# POWER.net
KiCad netlist of a schematic drawn in Altium Designer
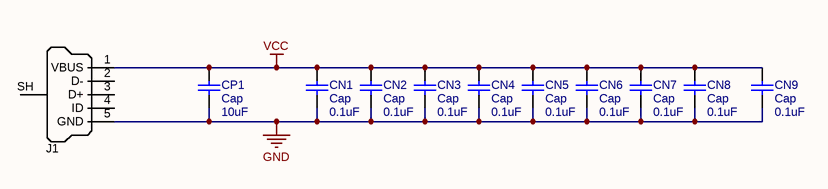
[diagram p0: POWER.SchDoc]

(export (version "E")
  (design (tool "Eeschema 10.0.6"))
  (components
    (comp (ref "CN1")
      (value "Cap")
      (footprint "CAPR10.16-11.5x3.6")
      (description "Capacitor")
      (fields (field (name "ALTIUM_VALUE") "0.1uF") (field (name "PUBLISHER") "Altium Limited"))
      (libsource (lib "Miscellaneous Devices") (part "Cap"))
    )
    (comp (ref "CN2")
      (value "Cap")
      (footprint "CAPR10.16-11.5x3.6")
      (description "Capacitor")
      (fields (field (name "ALTIUM_VALUE") "0.1uF") (field (name "PUBLISHER") "Altium Limited"))
      (libsource (lib "Miscellaneous Devices") (part "Cap"))
    )
    (comp (ref "CN3")
      (value "Cap")
      (footprint "CAPR10.16-11.5x3.6")
      (description "Capacitor")
      (fields (field (name "ALTIUM_VALUE") "0.1uF") (field (name "PUBLISHER") "Altium Limited"))
      (libsource (lib "Miscellaneous Devices") (part "Cap"))
    )
    (comp (ref "CN4")
      (value "Cap")
      (footprint "CAPR10.16-11.5x3.6")
      (description "Capacitor")
      (fields (field (name "ALTIUM_VALUE") "0.1uF") (field (name "PUBLISHER") "Altium Limited"))
      (libsource (lib "Miscellaneous Devices") (part "Cap"))
    )
    (comp (ref "CN5")
      (value "Cap")
      (footprint "CAPR10.16-11.5x3.6")
      (description "Capacitor")
      (fields (field (name "ALTIUM_VALUE") "0.1uF") (field (name "PUBLISHER") "Altium Limited"))
      (libsource (lib "Miscellaneous Devices") (part "Cap"))
    )
    (comp (ref "CN6")
      (value "Cap")
      (footprint "CAPR10.16-11.5x3.6")
      (description "Capacitor")
      (fields (field (name "ALTIUM_VALUE") "0.1uF") (field (name "PUBLISHER") "Altium Limited"))
      (libsource (lib "Miscellaneous Devices") (part "Cap"))
    )
    (comp (ref "CN7")
      (value "Cap")
      (footprint "CAPR10.16-11.5x3.6")
      (description "Capacitor")
      (fields (field (name "ALTIUM_VALUE") "0.1uF") (field (name "PUBLISHER") "Altium Limited"))
      (libsource (lib "Miscellaneous Devices") (part "Cap"))
    )
    (comp (ref "CN8")
      (value "Cap")
      (footprint "CAPR10.16-11.5x3.6")
      (description "Capacitor")
      (fields (field (name "ALTIUM_VALUE") "0.1uF") (field (name "PUBLISHER") "Altium Limited"))
      (libsource (lib "Miscellaneous Devices") (part "Cap"))
    )
    (comp (ref "CN9")
      (value "Cap")
      (footprint "CAPR10.16-11.5x3.6")
      (description "Capacitor")
      (fields (field (name "ALTIUM_VALUE") "0.1uF") (field (name "PUBLISHER") "Altium Limited"))
      (libsource (lib "Miscellaneous Devices") (part "Cap"))
    )
    (comp (ref "CP1")
      (value "Cap")
      (footprint "CAPE3.5mm")
      (description "Capacitor")
      (fields (field (name "ALTIUM_VALUE") "10uF") (field (name "PUBLISHER") "Altium Limited"))
      (libsource (lib "Miscellaneous Devices") (part "Cap"))
    )
    (comp (ref "J1")
      (value "USB Micro Type B (recommended if hand soldering)")
      (footprint "USB Micro B SMD")
      (description "Connector SMD-THD USB Micro Type B middle mount")
      (libsource (lib "PBL - Connectors") (part "USB_Micro_TypeB_FCI"))
    )
  )
  (nets
    (net (code "1") (name "GND") (class "Default")
      (node (ref "CN1") (pin "1") (pinfunction "1_1") (pintype "passive"))
      (node (ref "CN2") (pin "1") (pinfunction "1_1") (pintype "passive"))
      (node (ref "CN3") (pin "1") (pinfunction "1_1") (pintype "passive"))
      (node (ref "CN4") (pin "1") (pinfunction "1_1") (pintype "passive"))
      (node (ref "CN5") (pin "1") (pinfunction "1_1") (pintype "passive"))
      (node (ref "CN6") (pin "1") (pinfunction "1_1") (pintype "passive"))
      (node (ref "CN7") (pin "1") (pinfunction "1_1") (pintype "passive"))
      (node (ref "CN8") (pin "1") (pinfunction "1_1") (pintype "passive"))
      (node (ref "CN9") (pin "1") (pinfunction "1_1") (pintype "passive"))
      (node (ref "CP1") (pin "2") (pinfunction "2_2") (pintype "passive"))
      (node (ref "J1") (pin "5") (pinfunction "GND_5") (pintype "passive"))
    )
    (net (code "2") (name "VCC") (class "Default")
      (node (ref "CN1") (pin "2") (pinfunction "2_2") (pintype "passive"))
      (node (ref "CN2") (pin "2") (pinfunction "2_2") (pintype "passive"))
      (node (ref "CN3") (pin "2") (pinfunction "2_2") (pintype "passive"))
      (node (ref "CN4") (pin "2") (pinfunction "2_2") (pintype "passive"))
      (node (ref "CN5") (pin "2") (pinfunction "2_2") (pintype "passive"))
      (node (ref "CN6") (pin "2") (pinfunction "2_2") (pintype "passive"))
      (node (ref "CN7") (pin "2") (pinfunction "2_2") (pintype "passive"))
      (node (ref "CN8") (pin "2") (pinfunction "2_2") (pintype "passive"))
      (node (ref "CN9") (pin "2") (pinfunction "2_2") (pintype "passive"))
      (node (ref "CP1") (pin "1") (pinfunction "1_1") (pintype "passive"))
      (node (ref "J1") (pin "1") (pinfunction "VBUS_1") (pintype "passive"))
    )
    (net (code "3") (name "unconnected-(J1-D+-Pad3)") (class "Default")
      (node (ref "J1") (pin "3") (pinfunction "D+_3") (pintype "passive"))
    )
    (net (code "4") (name "unconnected-(J1-D--Pad2)") (class "Default")
      (node (ref "J1") (pin "2") (pinfunction "D-_2") (pintype "passive"))
    )
    (net (code "5") (name "unconnected-(J1-ID-Pad4)") (class "Default")
      (node (ref "J1") (pin "4") (pinfunction "ID_4") (pintype "passive"))
    )
    (net (code "6") (name "unconnected-(J1-Shell-PadSH)") (class "Default")
      (node (ref "J1") (pin "SH") (pinfunction "Shell_SH") (pintype "passive"))
    )
  )
)
